# Coil_Driver_Rev_A_CPU_Driver.net
KiCad netlist of a schematic drawn in Altium Designer
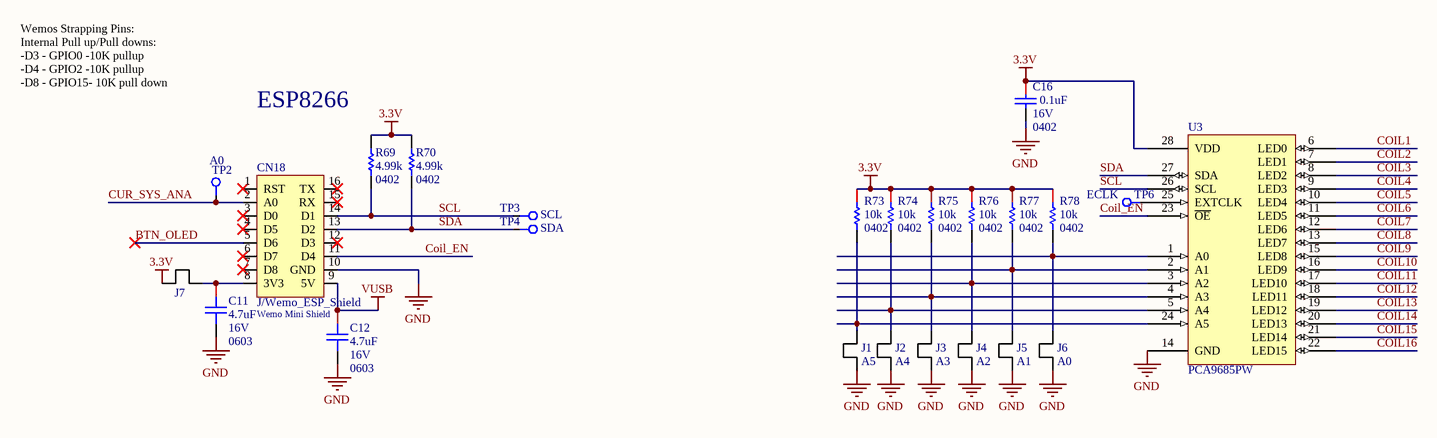
[diagram p0: Coil_Driver_Rev_A_CPU_Driver.SchDoc]

(export (version "E")
  (design (tool "Eeschema 10.0.6"))
  (components
    (comp (ref "C11")
      (value "4.7uF")
      (footprint "CAPC0603(1608)_L")
      (description "CAP CER 4.7uF 16V X5R 0603")
      (fields
        (field (name "VOLTAGE (RATED)") "16V")
        (field (name "PACKAGE (IMPERIAL)") "0603")
        (field (name "TOLERANCE") "10%")
      )
      (libsource (lib "OLogic Nexus Vault") (part "=Capacitance"))
    )
    (comp (ref "C12")
      (value "4.7uF")
      (footprint "CAPC0603(1608)_L")
      (description "CAP CER 4.7uF 16V X5R 0603")
      (fields
        (field (name "VOLTAGE (RATED)") "16V")
        (field (name "PACKAGE (IMPERIAL)") "0603")
        (field (name "TOLERANCE") "10%")
      )
      (libsource (lib "OLogic Nexus Vault") (part "=Capacitance"))
    )
    (comp (ref "C16")
      (value "0.1uF")
      (footprint "CAPC0402(1005)_L")
      (description "CAP CER 0.1UF 16v X7R 0402")
      (fields
        (field (name "VOLTAGE (RATED)") "16V")
        (field (name "PACKAGE (IMPERIAL)") "0402")
        (field (name "TOLERANCE") "10%")
      )
      (libsource (lib "") (part "=Capacitance_1"))
    )
    (comp (ref "CN18")
      (value "J/Wemo_ESP_Shield")
      (footprint "Wemos_d1")
      (description "Wemo Mini Shield for ESP-12")
      (fields (field (name "NAME") "Wemo Mini Shield"))
      (libsource (lib "Kyle_Lib_04-20-19") (part "J/Wemo_ESP_Shield"))
    )
    (comp (ref "J1")
      (value "A5")
      (footprint "RESC0603(1608)_L")
      (description "Solderable jumper for connecting things")
      (libsource (lib "OLogic Nexus Vault") (part "Sharks Tooth"))
    )
    (comp (ref "J2")
      (value "A4")
      (footprint "RESC0603(1608)_L")
      (description "Solderable jumper for connecting things")
      (libsource (lib "OLogic Nexus Vault") (part "Sharks Tooth"))
    )
    (comp (ref "J3")
      (value "A3")
      (footprint "RESC0603(1608)_L")
      (description "Solderable jumper for connecting things")
      (libsource (lib "OLogic Nexus Vault") (part "Sharks Tooth"))
    )
    (comp (ref "J4")
      (value "A2")
      (footprint "RESC0603(1608)_L")
      (description "Solderable jumper for connecting things")
      (libsource (lib "OLogic Nexus Vault") (part "Sharks Tooth"))
    )
    (comp (ref "J5")
      (value "A1")
      (footprint "RESC0603(1608)_L")
      (description "Solderable jumper for connecting things")
      (libsource (lib "OLogic Nexus Vault") (part "Sharks Tooth"))
    )
    (comp (ref "J6")
      (value "A0")
      (footprint "RESC0603(1608)_L")
      (description "Solderable jumper for connecting things")
      (libsource (lib "OLogic Nexus Vault") (part "Sharks Tooth"))
    )
    (comp (ref "J7")
      (value "Sharks Tooth 0603")
      (footprint "RESC0603(1608)_L")
      (description "Solderable jumper for connecting things")
      (libsource (lib "OLogic Nexus Vault") (part "Sharks Tooth"))
    )
    (comp (ref "R69")
      (value "4.99K 1%")
      (footprint "RESC0402(1005)_N")
      (description "4.99K 0402")
      (fields
        (field (name "MANUFACTURER") "Panasonic Electronic Components")
        (field (name "MANUFACTURER PART NUMBER") "ERJ-2RKF4991X")
        (field (name "RESISTANCE (OHMS)") "4.99k")
        (field (name "PACKAGE / CASE") "0402")
      )
      (libsource (lib "OLogic-Passive") (part "RES 4.99K OHM 1% 1/10W 0402"))
    )
    (comp (ref "R70")
      (value "4.99K 1%")
      (footprint "RESC0402(1005)_N")
      (description "4.99K 0402")
      (fields
        (field (name "MANUFACTURER") "Panasonic Electronic Components")
        (field (name "MANUFACTURER PART NUMBER") "ERJ-2RKF4991X")
        (field (name "RESISTANCE (OHMS)") "4.99k")
        (field (name "PACKAGE / CASE") "0402")
      )
      (libsource (lib "OLogic-Passive") (part "RES 4.99K OHM 1% 1/10W 0402"))
    )
    (comp (ref "R73")
      (value "RES 10K OHM 0.1% 1/16W 0402")
      (footprint "RESC0402(1005)_L")
      (description "10 kOhms ±0.1% 0.063W, 1/16W Chip Resistor 0402 (1005 Metric) Automotive AEC-Q200 Thin Film")
      (fields
        (field (name "TOLERANCE") "0.1%")
        (field (name "RESISTANCE") "10k")
        (field (name "CASE CODE (IMPERIAL)") "0402")
      )
      (libsource (lib "OLogic Nexus Vault") (part "OL_Resistor"))
    )
    (comp (ref "R74")
      (value "RES 10K OHM 0.1% 1/16W 0402")
      (footprint "RESC0402(1005)_L")
      (description "10 kOhms ±0.1% 0.063W, 1/16W Chip Resistor 0402 (1005 Metric) Automotive AEC-Q200 Thin Film")
      (fields
        (field (name "TOLERANCE") "0.1%")
        (field (name "RESISTANCE") "10k")
        (field (name "CASE CODE (IMPERIAL)") "0402")
      )
      (libsource (lib "OLogic Nexus Vault") (part "OL_Resistor"))
    )
    (comp (ref "R75")
      (value "RES 10K OHM 0.1% 1/16W 0402")
      (footprint "RESC0402(1005)_L")
      (description "10 kOhms ±0.1% 0.063W, 1/16W Chip Resistor 0402 (1005 Metric) Automotive AEC-Q200 Thin Film")
      (fields
        (field (name "TOLERANCE") "0.1%")
        (field (name "RESISTANCE") "10k")
        (field (name "CASE CODE (IMPERIAL)") "0402")
      )
      (libsource (lib "OLogic Nexus Vault") (part "OL_Resistor"))
    )
    (comp (ref "R76")
      (value "RES 10K OHM 0.1% 1/16W 0402")
      (footprint "RESC0402(1005)_L")
      (description "10 kOhms ±0.1% 0.063W, 1/16W Chip Resistor 0402 (1005 Metric) Automotive AEC-Q200 Thin Film")
      (fields
        (field (name "TOLERANCE") "0.1%")
        (field (name "RESISTANCE") "10k")
        (field (name "CASE CODE (IMPERIAL)") "0402")
      )
      (libsource (lib "OLogic Nexus Vault") (part "OL_Resistor"))
    )
    (comp (ref "R77")
      (value "RES 10K OHM 0.1% 1/16W 0402")
      (footprint "RESC0402(1005)_L")
      (description "10 kOhms ±0.1% 0.063W, 1/16W Chip Resistor 0402 (1005 Metric) Automotive AEC-Q200 Thin Film")
      (fields
        (field (name "TOLERANCE") "0.1%")
        (field (name "RESISTANCE") "10k")
        (field (name "CASE CODE (IMPERIAL)") "0402")
      )
      (libsource (lib "OLogic Nexus Vault") (part "OL_Resistor"))
    )
    (comp (ref "R78")
      (value "RES 10K OHM 0.1% 1/16W 0402")
      (footprint "RESC0402(1005)_L")
      (description "10 kOhms ±0.1% 0.063W, 1/16W Chip Resistor 0402 (1005 Metric) Automotive AEC-Q200 Thin Film")
      (fields
        (field (name "TOLERANCE") "0.1%")
        (field (name "RESISTANCE") "10k")
        (field (name "CASE CODE (IMPERIAL)") "0402")
      )
      (libsource (lib "OLogic Nexus Vault") (part "OL_Resistor"))
    )
    (comp (ref "TP2")
      (value "A0")
      (footprint "Pogo-Testpoint")
      (description "Test Point- Current one")
      (libsource (lib "OLogic Nexus Vault") (part "TestPoint"))
    )
    (comp (ref "TP3")
      (value "SCL")
      (footprint "Pogo-Testpoint")
      (description "Test Point- Current one")
      (libsource (lib "OLogic Nexus Vault") (part "TestPoint"))
    )
    (comp (ref "TP4")
      (value "SDA")
      (footprint "Pogo-Testpoint")
      (description "Test Point- Current one")
      (libsource (lib "OLogic Nexus Vault") (part "TestPoint"))
    )
    (comp (ref "TP6")
      (value "ECLK")
      (footprint "Pogo-Testpoint")
      (description "Test Point- Current one")
      (libsource (lib "OLogic Nexus Vault") (part "TestPoint"))
    )
    (comp (ref "U3")
      (value "PCA9685PW")
      (footprint "TSOP65P640X110-28N")
      (description "IC LED DRVR LIN DIM 25MA 28TSSOP / LED Driver 10000uA Supply Current 28-Pin TSSOP")
      (libsource (lib "OLogic Nexus Vault") (part "PCA9685PW-Symbol-1"))
    )
  )
  (nets
    (net (code "1") (name "/BTN_OLED") (class "Default")
      (node (ref "CN18") (pin "5") (pinfunction "D6_5") (pintype "power_in+no_connect"))
    )
    (net (code "2") (name "/COIL1") (class "Default")
      (node (ref "U3") (pin "6") (pinfunction "LED0_6") (pintype "bidirectional"))
    )
    (net (code "3") (name "/COIL2") (class "Default")
      (node (ref "U3") (pin "7") (pinfunction "LED1_7") (pintype "bidirectional"))
    )
    (net (code "4") (name "/COIL3") (class "Default")
      (node (ref "U3") (pin "8") (pinfunction "LED2_8") (pintype "bidirectional"))
    )
    (net (code "5") (name "/COIL4") (class "Default")
      (node (ref "U3") (pin "9") (pinfunction "LED3_9") (pintype "bidirectional"))
    )
    (net (code "6") (name "/COIL5") (class "Default")
      (node (ref "U3") (pin "10") (pinfunction "LED4_10") (pintype "bidirectional"))
    )
    (net (code "7") (name "/COIL6") (class "Default")
      (node (ref "U3") (pin "11") (pinfunction "LED5_11") (pintype "bidirectional"))
    )
    (net (code "8") (name "/COIL7") (class "Default")
      (node (ref "U3") (pin "12") (pinfunction "LED6_12") (pintype "bidirectional"))
    )
    (net (code "9") (name "/COIL8") (class "Default")
      (node (ref "U3") (pin "13") (pinfunction "LED7_13") (pintype "bidirectional"))
    )
    (net (code "10") (name "/COIL9") (class "Default")
      (node (ref "U3") (pin "15") (pinfunction "LED8_15") (pintype "bidirectional"))
    )
    (net (code "11") (name "/COIL10") (class "Default")
      (node (ref "U3") (pin "16") (pinfunction "LED9_16") (pintype "bidirectional"))
    )
    (net (code "12") (name "/COIL11") (class "Default")
      (node (ref "U3") (pin "17") (pinfunction "LED10_17") (pintype "bidirectional"))
    )
    (net (code "13") (name "/COIL12") (class "Default")
      (node (ref "U3") (pin "18") (pinfunction "LED11_18") (pintype "bidirectional"))
    )
    (net (code "14") (name "/COIL13") (class "Default")
      (node (ref "U3") (pin "19") (pinfunction "LED12_19") (pintype "bidirectional"))
    )
    (net (code "15") (name "/COIL14") (class "Default")
      (node (ref "U3") (pin "20") (pinfunction "LED13_20") (pintype "bidirectional"))
    )
    (net (code "16") (name "/COIL15") (class "Default")
      (node (ref "U3") (pin "21") (pinfunction "LED14_21") (pintype "bidirectional"))
    )
    (net (code "17") (name "/COIL16") (class "Default")
      (node (ref "U3") (pin "22") (pinfunction "LED15_22") (pintype "bidirectional"))
    )
    (net (code "18") (name "/CUR_SYS_ANA") (class "Default")
      (node (ref "CN18") (pin "2") (pinfunction "A0_2") (pintype "power_in"))
      (node (ref "TP2") (pin "1") (pinfunction "1_1") (pintype "passive"))
    )
    (net (code "19") (name "/Coil_EN") (class "Default")
      (node (ref "CN18") (pin "11") (pinfunction "D4_11") (pintype "power_in"))
      (node (ref "U3") (pin "23") (pinfunction "~{OE}_23") (pintype "input"))
    )
    (net (code "20") (name "/SCL") (class "Default")
      (node (ref "CN18") (pin "14") (pinfunction "D1_14") (pintype "power_in"))
      (node (ref "R69") (pin "1") (pinfunction "1_1") (pintype "passive"))
      (node (ref "TP3") (pin "1") (pinfunction "1_1") (pintype "passive"))
      (node (ref "U3") (pin "26") (pinfunction "SCL_26") (pintype "bidirectional"))
    )
    (net (code "21") (name "/SDA") (class "Default")
      (node (ref "CN18") (pin "13") (pinfunction "D2_13") (pintype "power_in"))
      (node (ref "R70") (pin "1") (pinfunction "1_1") (pintype "passive"))
      (node (ref "TP4") (pin "1") (pinfunction "1_1") (pintype "passive"))
      (node (ref "U3") (pin "27") (pinfunction "SDA_27") (pintype "bidirectional"))
    )
    (net (code "22") (name "3.3V") (class "Default")
      (node (ref "C16") (pin "1") (pinfunction "1_1") (pintype "passive"))
      (node (ref "J7") (pin "1") (pinfunction "1_1") (pintype "passive"))
      (node (ref "R69") (pin "2") (pinfunction "2_2") (pintype "passive"))
      (node (ref "R70") (pin "2") (pinfunction "2_2") (pintype "passive"))
      (node (ref "R73") (pin "1") (pinfunction "1_1") (pintype "passive"))
      (node (ref "R74") (pin "1") (pinfunction "1_1") (pintype "passive"))
      (node (ref "R75") (pin "1") (pinfunction "1_1") (pintype "passive"))
      (node (ref "R76") (pin "1") (pinfunction "1_1") (pintype "passive"))
      (node (ref "R77") (pin "1") (pinfunction "1_1") (pintype "passive"))
      (node (ref "R78") (pin "1") (pinfunction "1_1") (pintype "passive"))
      (node (ref "U3") (pin "28") (pinfunction "VDD_28") (pintype "power_in"))
    )
    (net (code "23") (name "GND") (class "Default")
      (node (ref "C11") (pin "2") (pinfunction "2_2") (pintype "passive"))
      (node (ref "C12") (pin "2") (pinfunction "2_2") (pintype "passive"))
      (node (ref "C16") (pin "2") (pinfunction "2_2") (pintype "passive"))
      (node (ref "CN18") (pin "10") (pinfunction "GND_10") (pintype "power_in"))
      (node (ref "J1") (pin "1") (pinfunction "1_1") (pintype "passive"))
      (node (ref "J2") (pin "1") (pinfunction "1_1") (pintype "passive"))
      (node (ref "J3") (pin "1") (pinfunction "1_1") (pintype "passive"))
      (node (ref "J4") (pin "1") (pinfunction "1_1") (pintype "passive"))
      (node (ref "J5") (pin "1") (pinfunction "1_1") (pintype "passive"))
      (node (ref "J6") (pin "1") (pinfunction "1_1") (pintype "passive"))
      (node (ref "U3") (pin "14") (pinfunction "GND_14") (pintype "power_in"))
    )
    (net (code "24") (name "Net-(CN18-3V3)") (class "Default")
      (node (ref "C11") (pin "1") (pinfunction "1_1") (pintype "passive"))
      (node (ref "CN18") (pin "8") (pinfunction "3V3_8") (pintype "power_in"))
      (node (ref "J7") (pin "2") (pinfunction "2_2") (pintype "passive"))
    )
    (net (code "25") (name "Net-(U3-A0)") (class "Default")
      (node (ref "J6") (pin "2") (pinfunction "2_2") (pintype "passive"))
      (node (ref "R78") (pin "2") (pinfunction "2_2") (pintype "passive"))
      (node (ref "U3") (pin "1") (pinfunction "A0_1") (pintype "input"))
    )
    (net (code "26") (name "Net-(U3-A1)") (class "Default")
      (node (ref "J5") (pin "2") (pinfunction "2_2") (pintype "passive"))
      (node (ref "R77") (pin "2") (pinfunction "2_2") (pintype "passive"))
      (node (ref "U3") (pin "2") (pinfunction "A1_2") (pintype "input"))
    )
    (net (code "27") (name "Net-(U3-A2)") (class "Default")
      (node (ref "J4") (pin "2") (pinfunction "2_2") (pintype "passive"))
      (node (ref "R76") (pin "2") (pinfunction "2_2") (pintype "passive"))
      (node (ref "U3") (pin "3") (pinfunction "A2_3") (pintype "input"))
    )
    (net (code "28") (name "Net-(U3-A3)") (class "Default")
      (node (ref "J3") (pin "2") (pinfunction "2_2") (pintype "passive"))
      (node (ref "R75") (pin "2") (pinfunction "2_2") (pintype "passive"))
      (node (ref "U3") (pin "4") (pinfunction "A3_4") (pintype "input"))
    )
    (net (code "29") (name "Net-(U3-A4)") (class "Default")
      (node (ref "J2") (pin "2") (pinfunction "2_2") (pintype "passive"))
      (node (ref "R74") (pin "2") (pinfunction "2_2") (pintype "passive"))
      (node (ref "U3") (pin "5") (pinfunction "A4_5") (pintype "input"))
    )
    (net (code "30") (name "Net-(U3-A5)") (class "Default")
      (node (ref "J1") (pin "2") (pinfunction "2_2") (pintype "passive"))
      (node (ref "R73") (pin "2") (pinfunction "2_2") (pintype "passive"))
      (node (ref "U3") (pin "24") (pinfunction "A5_24") (pintype "input"))
    )
    (net (code "31") (name "Net-(U3-EXTCLK)") (class "Default")
      (node (ref "TP6") (pin "1") (pinfunction "1_1") (pintype "passive"))
      (node (ref "U3") (pin "25") (pinfunction "EXTCLK_25") (pintype "input"))
    )
    (net (code "32") (name "VUSB") (class "Default")
      (node (ref "C12") (pin "1") (pinfunction "1_1") (pintype "passive"))
      (node (ref "CN18") (pin "9") (pinfunction "5V_9") (pintype "power_in"))
    )
    (net (code "33") (name "unconnected-(CN18-D0-Pad3)") (class "Default")
      (node (ref "CN18") (pin "3") (pinfunction "D0_3") (pintype "power_in+no_connect"))
    )
    (net (code "34") (name "unconnected-(CN18-D3-Pad12)") (class "Default")
      (node (ref "CN18") (pin "12") (pinfunction "D3_12") (pintype "power_in+no_connect"))
    )
    (net (code "35") (name "unconnected-(CN18-D5-Pad4)") (class "Default")
      (node (ref "CN18") (pin "4") (pinfunction "D5_4") (pintype "power_in+no_connect"))
    )
    (net (code "36") (name "unconnected-(CN18-D7-Pad6)") (class "Default")
      (node (ref "CN18") (pin "6") (pinfunction "D7_6") (pintype "power_in+no_connect"))
    )
    (net (code "37") (name "unconnected-(CN18-D8-Pad7)") (class "Default")
      (node (ref "CN18") (pin "7") (pinfunction "D8_7") (pintype "power_in+no_connect"))
    )
    (net (code "38") (name "unconnected-(CN18-RST-Pad1)") (class "Default")
      (node (ref "CN18") (pin "1") (pinfunction "RST_1") (pintype "power_in+no_connect"))
    )
    (net (code "39") (name "unconnected-(CN18-RX-Pad15)") (class "Default")
      (node (ref "CN18") (pin "15") (pinfunction "RX_15") (pintype "power_in+no_connect"))
    )
    (net (code "40") (name "unconnected-(CN18-TX-Pad16)") (class "Default")
      (node (ref "CN18") (pin "16") (pinfunction "TX_16") (pintype "power_in+no_connect"))
    )
  )
)
